# pico.net
KiCad netlist of a schematic drawn in Altium Designer
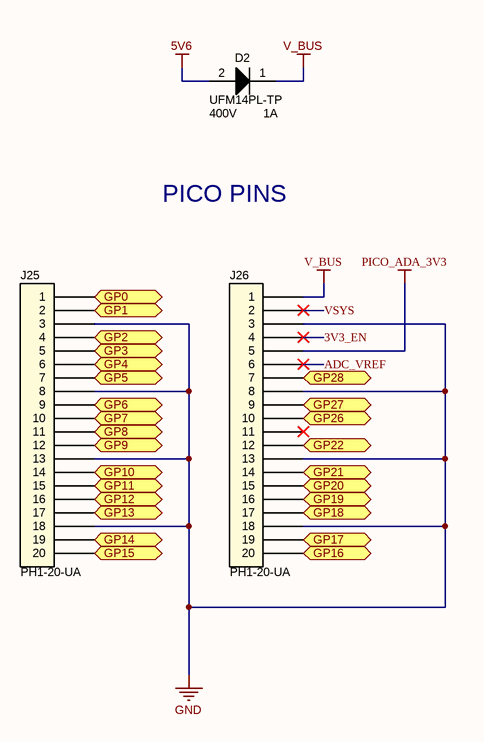
[diagram p0: pico.SchDoc]

(export (version "E")
  (design (tool "Eeschema 10.0.6"))
  (components
    (comp (ref "D2")
      (value "UFM14PL-TP")
      (footprint "SODFL358X135-2N")
      (description "DIODE GEN PURP 400V 1A SOD123FL")
      (fields
        (field (name "MFR") "Micro Commercial Co")
        (field (name "CURRENT RATING") "1A")
        (field (name "VOLTAGE RATING") "400V")
      )
      (libsource (lib "General_Library") (part "CMP-010-0012"))
    )
    (comp (ref "J25")
      (value "PH1-20-UA")
      (footprint "CONN_ADAM_TECH_PH1-20-UA")
      (description "CONN HEADER VERT 20POS 2.54MM GOLD")
      (fields (field (name "MFR") "Adam Tech"))
      (libsource (lib "General_Library") (part "CMP-007-0067"))
    )
    (comp (ref "J26")
      (value "PH1-20-UA")
      (footprint "CONN_ADAM_TECH_PH1-20-UA")
      (description "CONN HEADER VERT 20POS 2.54MM GOLD")
      (fields (field (name "MFR") "Adam Tech"))
      (libsource (lib "General_Library") (part "CMP-007-0067"))
    )
  )
  (nets
    (net (code "1") (name "/3V3_EN") (class "Default")
      (node (ref "J26") (pin "4") (pinfunction "4_4") (pintype "passive+no_connect"))
    )
    (net (code "2") (name "/ADC_VREF") (class "Default")
      (node (ref "J26") (pin "6") (pinfunction "6_6") (pintype "passive+no_connect"))
    )
    (net (code "3") (name "/GP0") (class "Default")
      (node (ref "J25") (pin "1") (pinfunction "1_1") (pintype "passive"))
    )
    (net (code "4") (name "/GP1") (class "Default")
      (node (ref "J25") (pin "2") (pinfunction "2_2") (pintype "passive"))
    )
    (net (code "5") (name "/GP2") (class "Default")
      (node (ref "J25") (pin "4") (pinfunction "4_4") (pintype "passive"))
    )
    (net (code "6") (name "/GP3") (class "Default")
      (node (ref "J25") (pin "5") (pinfunction "5_5") (pintype "passive"))
    )
    (net (code "7") (name "/GP4") (class "Default")
      (node (ref "J25") (pin "6") (pinfunction "6_6") (pintype "passive"))
    )
    (net (code "8") (name "/GP5") (class "Default")
      (node (ref "J25") (pin "7") (pinfunction "7_7") (pintype "passive"))
    )
    (net (code "9") (name "/GP6") (class "Default")
      (node (ref "J25") (pin "9") (pinfunction "9_9") (pintype "passive"))
    )
    (net (code "10") (name "/GP7") (class "Default")
      (node (ref "J25") (pin "10") (pinfunction "10_10") (pintype "passive"))
    )
    (net (code "11") (name "/GP8") (class "Default")
      (node (ref "J25") (pin "11") (pinfunction "11_11") (pintype "passive"))
    )
    (net (code "12") (name "/GP9") (class "Default")
      (node (ref "J25") (pin "12") (pinfunction "12_12") (pintype "passive"))
    )
    (net (code "13") (name "/GP10") (class "Default")
      (node (ref "J25") (pin "14") (pinfunction "14_14") (pintype "passive"))
    )
    (net (code "14") (name "/GP11") (class "Default")
      (node (ref "J25") (pin "15") (pinfunction "15_15") (pintype "passive"))
    )
    (net (code "15") (name "/GP12") (class "Default")
      (node (ref "J25") (pin "16") (pinfunction "16_16") (pintype "passive"))
    )
    (net (code "16") (name "/GP13") (class "Default")
      (node (ref "J25") (pin "17") (pinfunction "17_17") (pintype "passive"))
    )
    (net (code "17") (name "/GP14") (class "Default")
      (node (ref "J25") (pin "19") (pinfunction "19_19") (pintype "passive"))
    )
    (net (code "18") (name "/GP15") (class "Default")
      (node (ref "J25") (pin "20") (pinfunction "20_20") (pintype "passive"))
    )
    (net (code "19") (name "/GP16") (class "Default")
      (node (ref "J26") (pin "20") (pinfunction "20_20") (pintype "passive"))
    )
    (net (code "20") (name "/GP17") (class "Default")
      (node (ref "J26") (pin "19") (pinfunction "19_19") (pintype "passive"))
    )
    (net (code "21") (name "/GP18") (class "Default")
      (node (ref "J26") (pin "17") (pinfunction "17_17") (pintype "passive"))
    )
    (net (code "22") (name "/GP19") (class "Default")
      (node (ref "J26") (pin "16") (pinfunction "16_16") (pintype "passive"))
    )
    (net (code "23") (name "/GP20") (class "Default")
      (node (ref "J26") (pin "15") (pinfunction "15_15") (pintype "passive"))
    )
    (net (code "24") (name "/GP21") (class "Default")
      (node (ref "J26") (pin "14") (pinfunction "14_14") (pintype "passive"))
    )
    (net (code "25") (name "/GP22") (class "Default")
      (node (ref "J26") (pin "12") (pinfunction "12_12") (pintype "passive"))
    )
    (net (code "26") (name "/GP26") (class "Default")
      (node (ref "J26") (pin "10") (pinfunction "10_10") (pintype "passive"))
    )
    (net (code "27") (name "/GP27") (class "Default")
      (node (ref "J26") (pin "9") (pinfunction "9_9") (pintype "passive"))
    )
    (net (code "28") (name "/GP28") (class "Default")
      (node (ref "J26") (pin "7") (pinfunction "7_7") (pintype "passive"))
    )
    (net (code "29") (name "/VSYS") (class "Default")
      (node (ref "J26") (pin "2") (pinfunction "2_2") (pintype "passive+no_connect"))
    )
    (net (code "30") (name "5V6") (class "Default")
      (node (ref "D2") (pin "2") (pinfunction "Anode_2") (pintype "passive"))
    )
    (net (code "31") (name "GND") (class "Default")
      (node (ref "J25") (pin "13") (pinfunction "13_13") (pintype "passive"))
      (node (ref "J25") (pin "18") (pinfunction "18_18") (pintype "passive"))
      (node (ref "J25") (pin "3") (pinfunction "3_3") (pintype "passive"))
      (node (ref "J25") (pin "8") (pinfunction "8_8") (pintype "passive"))
      (node (ref "J26") (pin "13") (pinfunction "13_13") (pintype "passive"))
      (node (ref "J26") (pin "18") (pinfunction "18_18") (pintype "passive"))
      (node (ref "J26") (pin "3") (pinfunction "3_3") (pintype "passive"))
      (node (ref "J26") (pin "8") (pinfunction "8_8") (pintype "passive"))
    )
    (net (code "32") (name "PICO_ADA_3V3") (class "Default")
      (node (ref "J26") (pin "5") (pinfunction "5_5") (pintype "passive"))
    )
    (net (code "33") (name "V_BUS") (class "Default")
      (node (ref "D2") (pin "1") (pinfunction "Cathode_1") (pintype "passive"))
      (node (ref "J26") (pin "1") (pinfunction "1_1") (pintype "passive"))
    )
    (net (code "34") (name "unconnected-(J26-Pad11)") (class "Default")
      (node (ref "J26") (pin "11") (pinfunction "11_11") (pintype "passive+no_connect"))
    )
  )
)
